# sfp_wrapper.net
KiCad netlist of a schematic drawn in Altium Designer
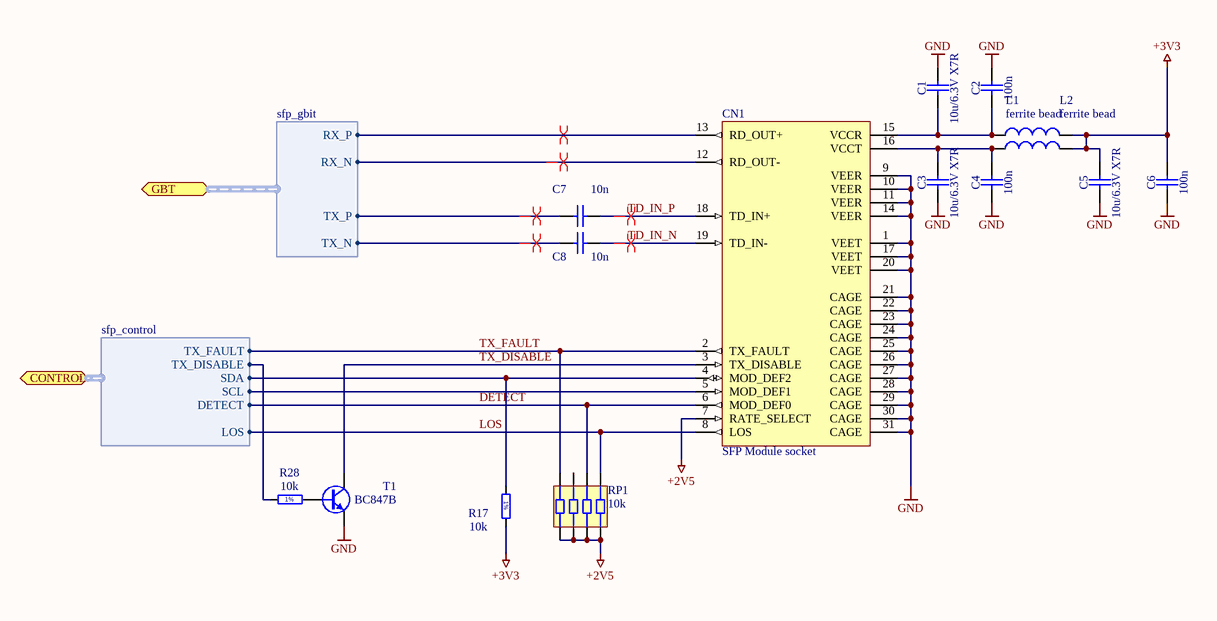
[diagram p0: sfp_wrapper.SchDoc]

(export (version "E")
  (design (tool "Eeschema 10.0.6"))
  (components
    (comp (ref "C1")
      (value "10u/6.3V X7R")
      (footprint "CAPC3216X140N")
      (description "Non-polarised capacitor")
      (fields
        (field (name "PART NUMBER") "CC1206_10UF_10V_10%_X7R")
        (field (name "VOLTAGE") "10V")
        (field (name "AUTHOR") "CERN DEM JLC")
      )
      (libsource (lib "Capacitors") (part "Capacitor - non polarized"))
    )
    (comp (ref "C2")
      (value "100n")
      (footprint "CAPC1608X87N")
      (description "Non-polarised capacitor")
      (fields
        (field (name "PART NUMBER") "CC0603_100NF_50V_10%_X7R")
        (field (name "VOLTAGE") "50V")
        (field (name "AUTHOR") "CERN DEM JLC")
      )
      (libsource (lib "Capacitors") (part "Capacitor - non polarized"))
    )
    (comp (ref "C3")
      (value "10u/6.3V X7R")
      (footprint "CAPC3216X140N")
      (description "Non-polarised capacitor")
      (fields
        (field (name "PART NUMBER") "CC1206_10UF_10V_10%_X7R")
        (field (name "VOLTAGE") "10V")
        (field (name "AUTHOR") "CERN DEM JLC")
      )
      (libsource (lib "Capacitors") (part "Capacitor - non polarized"))
    )
    (comp (ref "C4")
      (value "100n")
      (footprint "CAPC1608X87N")
      (description "Non-polarised capacitor")
      (fields
        (field (name "PART NUMBER") "CC0603_100NF_50V_10%_X7R")
        (field (name "VOLTAGE") "50V")
        (field (name "AUTHOR") "CERN DEM JLC")
      )
      (libsource (lib "Capacitors") (part "Capacitor - non polarized"))
    )
    (comp (ref "C5")
      (value "10u/6.3V X7R")
      (footprint "CAPC3216X140N")
      (description "Non-polarised capacitor")
      (fields
        (field (name "PART NUMBER") "CC1206_10UF_10V_10%_X7R")
        (field (name "VOLTAGE") "10V")
        (field (name "AUTHOR") "CERN DEM JLC")
      )
      (libsource (lib "Capacitors") (part "Capacitor - non polarized"))
    )
    (comp (ref "C6")
      (value "100n")
      (footprint "CAPC1608X87N")
      (description "Non-polarised capacitor")
      (fields
        (field (name "PART NUMBER") "CC0603_100NF_50V_10%_X7R")
        (field (name "VOLTAGE") "50V")
        (field (name "AUTHOR") "CERN DEM JLC")
      )
      (libsource (lib "Capacitors") (part "Capacitor - non polarized"))
    )
    (comp (ref "C7")
      (value "10n")
      (footprint "CAPC1608X87N")
      (description "Non-polarised capacitor")
      (fields
        (field (name "PART NUMBER") "CC0603_10NF_50V_10%_X7R")
        (field (name "VOLTAGE") "50V")
        (field (name "AUTHOR") "CERN DEM JLC")
      )
      (libsource (lib "Capacitors") (part "Capacitor - non polarized"))
    )
    (comp (ref "C8")
      (value "10n")
      (footprint "CAPC1608X87N")
      (description "Non-polarised capacitor")
      (fields
        (field (name "PART NUMBER") "CC0603_10NF_50V_10%_X7R")
        (field (name "VOLTAGE") "50V")
        (field (name "AUTHOR") "CERN DEM JLC")
      )
      (libsource (lib "Capacitors") (part "Capacitor - non polarized"))
    )
    (comp (ref "CN1")
      (value "SFP Module socket")
      (footprint "SFP_SINGLE_PORT")
      (description "Socket for SFP module")
      (libsource (lib "wr_switch") (part "SFP_SOCKET_SINGLE"))
    )
    (comp (ref "L1")
      (value "ferrite bead")
      (footprint "INDC2012-0805")
      (description "Ferrite bead")
      (fields (field (name "Comment") "Inductor") (field (name "PUBLISHER") "Altium Limited"))
      (libsource (lib "Miscellaneous Devices") (part "Inductor"))
    )
    (comp (ref "L2")
      (value "ferrite bead")
      (footprint "INDC2012-0805")
      (description "Ferrite bead")
      (fields (field (name "Comment") "Inductor") (field (name "PUBLISHER") "Altium Limited"))
      (libsource (lib "Miscellaneous Devices") (part "Inductor"))
    )
    (comp (ref "R17")
      (value "10k")
      (footprint "RESC1608X55N")
      (description "Resistor - 1%")
      (fields
        (field (name "PART NUMBER") "R0603_10K_1%_0.1W_100PPM")
        (field (name "POWER") "0.1W")
        (field (name "AUTHOR") "CERN DEM JLC")
      )
      (libsource (lib "Resistors") (part "Resistor - 1%"))
    )
    (comp (ref "R28")
      (value "10k")
      (footprint "RESC1608X55N")
      (description "Resistor - 1%")
      (fields
        (field (name "PART NUMBER") "R0603_10K_1%_0.1W_100PPM")
        (field (name "POWER") "0.1W")
        (field (name "AUTHOR") "CERN DEM JLC")
      )
      (libsource (lib "Resistors") (part "Resistor - 1%"))
    )
    (comp (ref "RP1")
      (value "10k")
      (footprint "CAY-16")
      (description "Resistor network 1206 (4x0402) Maritex RAC4Xxxx")
      (libsource (lib "LIBRARY_SCH") (part "RES_ARRAY_1206"))
    )
    (comp (ref "T1")
      (value "BC847B")
      (footprint "SOT95P230X110-3N")
      (description "NPN Transistor")
      (fields (field (name "MANUFACTURER") "NXP SEMICONDUCTORS") (field (name "AUTHOR") "CERN DEM JLC"))
      (libsource (lib "ICs And Semiconductors") (part "NPN B1 E2 C3"))
    )
  )
  (nets
    (net (code "3") (name "+2V5") (class "Default")
      (node (ref "CN1") (pin "7") (pinfunction "RATE_SELECT_7") (pintype "input"))
      (node (ref "RP1") (pin "1") (pinfunction "1_1") (pintype "passive"))
      (node (ref "RP1") (pin "2") (pinfunction "2_2") (pintype "passive"))
      (node (ref "RP1") (pin "3") (pinfunction "3_3") (pintype "passive"))
      (node (ref "RP1") (pin "4") (pinfunction "4_4") (pintype "passive"))
    )
    (net (code "4") (name "+3V3") (class "Default")
      (node (ref "C5") (pin "2") (pinfunction "2_2") (pintype "passive"))
      (node (ref "C6") (pin "2") (pinfunction "2_2") (pintype "passive"))
      (node (ref "L1") (pin "2") (pinfunction "2_2") (pintype "passive"))
      (node (ref "L2") (pin "2") (pinfunction "2_2") (pintype "passive"))
      (node (ref "R17") (pin "2") (pinfunction "2_2") (pintype "passive"))
    )
    (net (code "5") (name "/DETECT") (class "Default")
      (node (ref "CN1") (pin "6") (pinfunction "MOD_DEF0_6") (pintype "output"))
      (node (ref "RP1") (pin "6") (pinfunction "6_6") (pintype "passive"))
    )
    (net (code "6") (name "/LOS") (class "Default")
      (node (ref "CN1") (pin "8") (pinfunction "LOS_8") (pintype "output"))
      (node (ref "RP1") (pin "5") (pinfunction "5_5") (pintype "passive"))
    )
    (net (code "7") (name "/RX_N") (class "Default")
      (node (ref "CN1") (pin "12") (pinfunction "RD_OUT-_12") (pintype "output"))
    )
    (net (code "8") (name "/RX_P") (class "Default")
      (node (ref "CN1") (pin "13") (pinfunction "RD_OUT+_13") (pintype "output"))
    )
    (net (code "9") (name "/SCL") (class "Default")
      (node (ref "CN1") (pin "5") (pinfunction "MOD_DEF1_5") (pintype "input"))
    )
    (net (code "10") (name "/SDA") (class "Default")
      (node (ref "CN1") (pin "4") (pinfunction "MOD_DEF2_4") (pintype "bidirectional"))
      (node (ref "R17") (pin "1") (pinfunction "1_1") (pintype "passive"))
    )
    (net (code "11") (name "/TD_IN_N") (class "Default")
      (node (ref "C8") (pin "2") (pinfunction "2_2") (pintype "passive"))
      (node (ref "CN1") (pin "19") (pinfunction "TD_IN-_19") (pintype "input"))
    )
    (net (code "12") (name "/TD_IN_P") (class "Default")
      (node (ref "C7") (pin "2") (pinfunction "2_2") (pintype "passive"))
      (node (ref "CN1") (pin "18") (pinfunction "TD_IN+_18") (pintype "input"))
    )
    (net (code "13") (name "/TX_DISABLE") (class "Default")
      (node (ref "CN1") (pin "3") (pinfunction "TX_DISABLE_3") (pintype "input"))
      (node (ref "T1") (pin "3") (pinfunction "C_3") (pintype "passive"))
    )
    (net (code "14") (name "/TX_FAULT") (class "Default")
      (node (ref "CN1") (pin "2") (pinfunction "TX_FAULT_2") (pintype "output"))
      (node (ref "RP1") (pin "8") (pinfunction "8_8") (pintype "passive"))
    )
    (net (code "15") (name "/TX_N") (class "Default")
      (node (ref "C8") (pin "1") (pinfunction "1_1") (pintype "passive"))
    )
    (net (code "16") (name "/TX_P") (class "Default")
      (node (ref "C7") (pin "1") (pinfunction "1_1") (pintype "passive"))
    )
    (net (code "19") (name "GND") (class "Default")
      (node (ref "C1") (pin "2") (pinfunction "2_2") (pintype "passive"))
      (node (ref "C2") (pin "2") (pinfunction "2_2") (pintype "passive"))
      (node (ref "C3") (pin "1") (pinfunction "1_1") (pintype "passive"))
      (node (ref "C4") (pin "1") (pinfunction "1_1") (pintype "passive"))
      (node (ref "C5") (pin "1") (pinfunction "1_1") (pintype "passive"))
      (node (ref "C6") (pin "1") (pinfunction "1_1") (pintype "passive"))
      (node (ref "CN1") (pin "1") (pinfunction "VEET_1") (pintype "power_in"))
      (node (ref "CN1") (pin "10") (pinfunction "VEER_10") (pintype "power_in"))
      (node (ref "CN1") (pin "11") (pinfunction "VEER_11") (pintype "power_in"))
      (node (ref "CN1") (pin "14") (pinfunction "VEER_14") (pintype "power_in"))
      (node (ref "CN1") (pin "17") (pinfunction "VEET_17") (pintype "power_in"))
      (node (ref "CN1") (pin "20") (pinfunction "VEET_20") (pintype "power_in"))
      (node (ref "CN1") (pin "21") (pinfunction "CAGE_21") (pintype "power_in"))
      (node (ref "CN1") (pin "22") (pinfunction "CAGE_22") (pintype "power_in"))
      (node (ref "CN1") (pin "23") (pinfunction "CAGE_23") (pintype "power_in"))
      (node (ref "CN1") (pin "24") (pinfunction "CAGE_24") (pintype "power_in"))
      (node (ref "CN1") (pin "25") (pinfunction "CAGE_25") (pintype "power_in"))
      (node (ref "CN1") (pin "26") (pinfunction "CAGE_26") (pintype "power_in"))
      (node (ref "CN1") (pin "27") (pinfunction "CAGE_27") (pintype "power_in"))
      (node (ref "CN1") (pin "28") (pinfunction "CAGE_28") (pintype "power_in"))
      (node (ref "CN1") (pin "29") (pinfunction "CAGE_29") (pintype "power_in"))
      (node (ref "CN1") (pin "30") (pinfunction "CAGE_30") (pintype "power_in"))
      (node (ref "CN1") (pin "31") (pinfunction "CAGE_31") (pintype "power_in"))
      (node (ref "CN1") (pin "9") (pinfunction "VEER_9") (pintype "power_in"))
      (node (ref "T1") (pin "2") (pinfunction "E_2") (pintype "passive"))
    )
    (net (code "20") (name "Net-(CN1-VCCR)") (class "Default")
      (node (ref "C1") (pin "1") (pinfunction "1_1") (pintype "passive"))
      (node (ref "C2") (pin "1") (pinfunction "1_1") (pintype "passive"))
      (node (ref "CN1") (pin "15") (pinfunction "VCCR_15") (pintype "power_in"))
      (node (ref "L2") (pin "1") (pinfunction "1_1") (pintype "passive"))
    )
    (net (code "21") (name "Net-(CN1-VCCT)") (class "Default")
      (node (ref "C3") (pin "2") (pinfunction "2_2") (pintype "passive"))
      (node (ref "C4") (pin "2") (pinfunction "2_2") (pintype "passive"))
      (node (ref "CN1") (pin "16") (pinfunction "VCCT_16") (pintype "power_in"))
      (node (ref "L1") (pin "1") (pinfunction "1_1") (pintype "passive"))
    )
    (net (code "22") (name "Net-(T1-B)") (class "Default")
      (node (ref "R28") (pin "2") (pinfunction "2_2") (pintype "passive"))
      (node (ref "T1") (pin "1") (pinfunction "B_1") (pintype "passive"))
    )
    (net (code "23") (name "unconnected-(R28-Pad1)") (class "Default")
      (node (ref "R28") (pin "1") (pinfunction "1_1") (pintype "passive"))
    )
    (net (code "24") (name "unconnected-(RP1-Pad7)") (class "Default")
      (node (ref "RP1") (pin "7") (pinfunction "7_7") (pintype "passive"))
    )
  )
)
